# toplayer.net
KiCad netlist of a schematic drawn in Altium Designer
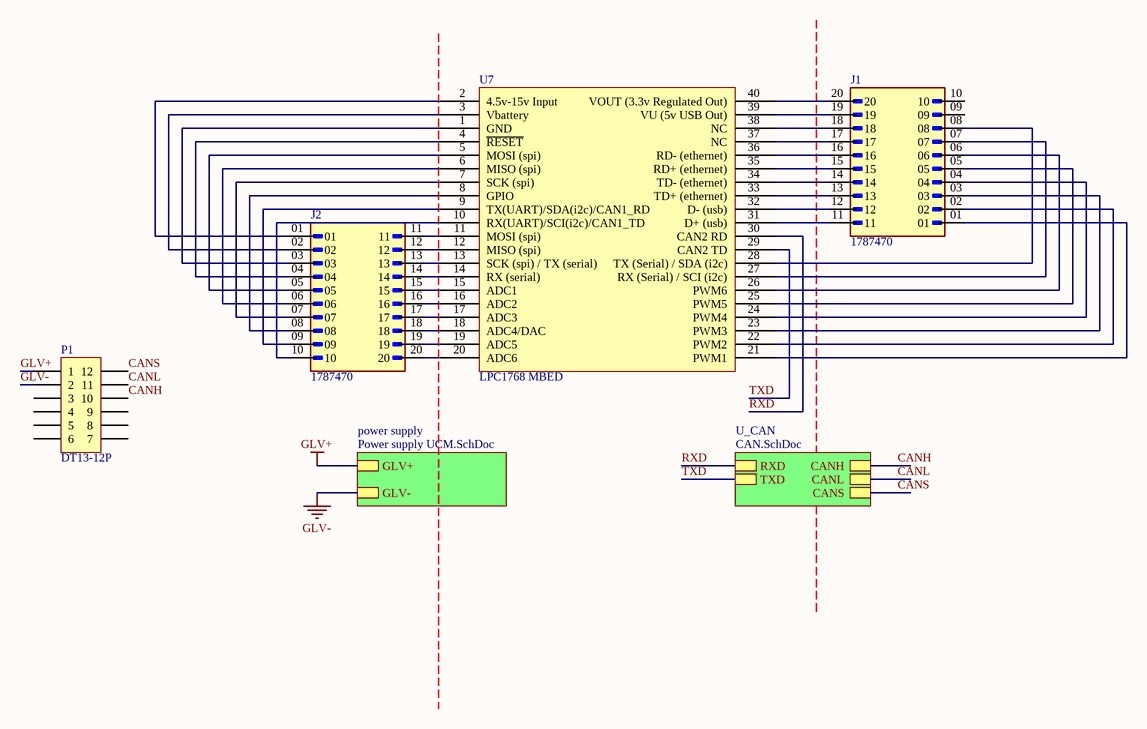
[diagram p0: toplayer.SchDoc]

(export (version "E")
  (design (tool "Eeschema 10.0.6"))
  (components
    (comp (ref "J1") (value "1787470") (footprint "PHOENIX_1787470") (libsource (lib "") (part "1787470_1")))
    (comp (ref "J2")
      (value "1787470")
      (footprint "PHOENIX_1787470")
      (libsource (lib "1787470") (part "1787470"))
    )
    (comp (ref "P1")
      (value "DT13-12P")
      (footprint "DT13-12P")
      (fields (field (name "DIGIKEY PART NUMBER") "1734-1451-ND") (field (name "CONTACT") "Nickel"))
      (libsource (lib "ts_19-standard-connectors") (part "DT13-12P"))
    )
    (comp (ref "U7")
      (value "LPC1768 MBED")
      (footprint "LPC1768 MBED")
      (description "ARM M3 mBed Enabled Microcontroller")
      (fields (field (name "MANUFACTURER") "NXP") (field (name "DIGIKEY PART NUMBER") "568-4916-ND"))
      (libsource (lib "ts_19-standard-library") (part "LPC1768 MBED"))
    )
  )
  (nets
    (net (code "1") (name "/CANH") (class "Default")
      (node (ref "P1") (pin "10") (pinfunction "10_10") (pintype "passive"))
    )
    (net (code "2") (name "/CANL") (class "Default")
      (node (ref "P1") (pin "11") (pinfunction "11_11") (pintype "passive"))
    )
    (net (code "3") (name "/CANS") (class "Default")
      (node (ref "P1") (pin "12") (pinfunction "12_12") (pintype "passive"))
    )
    (net (code "4") (name "/RXD") (class "Default")
      (node (ref "U7") (pin "30") (pinfunction "CAN2_RD_30") (pintype "passive"))
    )
    (net (code "5") (name "/TXD") (class "Default")
      (node (ref "U7") (pin "29") (pinfunction "CAN2_TD_29") (pintype "passive"))
    )
    (net (code "6") (name "GLV+") (class "Default")
      (node (ref "P1") (pin "1") (pinfunction "1_1") (pintype "power_in"))
    )
    (net (code "7") (name "GLV-") (class "Default")
      (node (ref "P1") (pin "2") (pinfunction "2_2") (pintype "power_in"))
    )
    (net (code "8") (name "Net-(J1-Pad17)") (class "Default")
      (node (ref "J1") (pin "17") (pinfunction "17_17") (pintype "passive"))
      (node (ref "U7") (pin "37") (pinfunction "NC_37") (pintype "passive"))
    )
    (net (code "9") (name "Net-(J1-Pad18)") (class "Default")
      (node (ref "J1") (pin "18") (pinfunction "18_18") (pintype "passive"))
      (node (ref "U7") (pin "38") (pinfunction "NC_38") (pintype "passive"))
    )
    (net (code "10") (name "Net-(J2-Pad05)") (class "Default")
      (node (ref "J2") (pin "05") (pinfunction "05_05") (pintype "passive"))
      (node (ref "U7") (pin "5") (pinfunction "MOSI_(spi)_5") (pintype "passive"))
    )
    (net (code "11") (name "Net-(J2-Pad06)") (class "Default")
      (node (ref "J2") (pin "06") (pinfunction "06_06") (pintype "passive"))
      (node (ref "U7") (pin "6") (pinfunction "MISO_(spi)_6") (pintype "passive"))
    )
    (net (code "12") (name "Net-(J2-Pad11)") (class "Default")
      (node (ref "J2") (pin "11") (pinfunction "11_11") (pintype "passive"))
      (node (ref "U7") (pin "11") (pinfunction "MOSI_(spi)_11") (pintype "passive"))
    )
    (net (code "13") (name "Net-(J2-Pad12)") (class "Default")
      (node (ref "J2") (pin "12") (pinfunction "12_12") (pintype "passive"))
      (node (ref "U7") (pin "12") (pinfunction "MISO_(spi)_12") (pintype "passive"))
    )
    (net (code "14") (name "Net-(U7-4.5v-15v_Input)") (class "Default")
      (node (ref "J2") (pin "01") (pinfunction "01_01") (pintype "passive"))
      (node (ref "U7") (pin "2") (pinfunction "4.5v-15v_Input_2") (pintype "passive"))
    )
    (net (code "15") (name "Net-(U7-ADC1)") (class "Default")
      (node (ref "J2") (pin "15") (pinfunction "15_15") (pintype "passive"))
      (node (ref "U7") (pin "15") (pinfunction "ADC1_15") (pintype "passive"))
    )
    (net (code "16") (name "Net-(U7-ADC2)") (class "Default")
      (node (ref "J2") (pin "16") (pinfunction "16_16") (pintype "passive"))
      (node (ref "U7") (pin "16") (pinfunction "ADC2_16") (pintype "passive"))
    )
    (net (code "17") (name "Net-(U7-ADC3)") (class "Default")
      (node (ref "J2") (pin "17") (pinfunction "17_17") (pintype "passive"))
      (node (ref "U7") (pin "17") (pinfunction "ADC3_17") (pintype "passive"))
    )
    (net (code "18") (name "Net-(U7-ADC4{slash}DAC)") (class "Default")
      (node (ref "J2") (pin "18") (pinfunction "18_18") (pintype "passive"))
      (node (ref "U7") (pin "18") (pinfunction "ADC4/DAC_18") (pintype "passive"))
    )
    (net (code "19") (name "Net-(U7-ADC5)") (class "Default")
      (node (ref "J2") (pin "19") (pinfunction "19_19") (pintype "passive"))
      (node (ref "U7") (pin "19") (pinfunction "ADC5_19") (pintype "passive"))
    )
    (net (code "20") (name "Net-(U7-ADC6)") (class "Default")
      (node (ref "J2") (pin "20") (pinfunction "20_20") (pintype "passive"))
      (node (ref "U7") (pin "20") (pinfunction "ADC6_20") (pintype "passive"))
    )
    (net (code "21") (name "Net-(U7-D+_(usb))") (class "Default")
      (node (ref "J1") (pin "11") (pinfunction "11_11") (pintype "passive"))
      (node (ref "U7") (pin "31") (pinfunction "D+_(usb)_31") (pintype "passive"))
    )
    (net (code "22") (name "Net-(U7-D-_(usb))") (class "Default")
      (node (ref "J1") (pin "12") (pinfunction "12_12") (pintype "passive"))
      (node (ref "U7") (pin "32") (pinfunction "D-_(usb)_32") (pintype "passive"))
    )
    (net (code "23") (name "Net-(U7-GND)") (class "Default")
      (node (ref "J2") (pin "03") (pinfunction "03_03") (pintype "passive"))
      (node (ref "U7") (pin "1") (pinfunction "GND_1") (pintype "passive"))
    )
    (net (code "24") (name "Net-(U7-GPIO)") (class "Default")
      (node (ref "J2") (pin "08") (pinfunction "08_08") (pintype "passive"))
      (node (ref "U7") (pin "8") (pinfunction "GPIO_8") (pintype "passive"))
    )
    (net (code "25") (name "Net-(U7-PWM1)") (class "Default")
      (node (ref "J1") (pin "01") (pinfunction "01_01") (pintype "passive"))
      (node (ref "U7") (pin "21") (pinfunction "PWM1_21") (pintype "passive"))
    )
    (net (code "26") (name "Net-(U7-PWM2)") (class "Default")
      (node (ref "J1") (pin "02") (pinfunction "02_02") (pintype "passive"))
      (node (ref "U7") (pin "22") (pinfunction "PWM2_22") (pintype "passive"))
    )
    (net (code "27") (name "Net-(U7-PWM3)") (class "Default")
      (node (ref "J1") (pin "03") (pinfunction "03_03") (pintype "passive"))
      (node (ref "U7") (pin "23") (pinfunction "PWM3_23") (pintype "passive"))
    )
    (net (code "28") (name "Net-(U7-PWM4)") (class "Default")
      (node (ref "J1") (pin "04") (pinfunction "04_04") (pintype "passive"))
      (node (ref "U7") (pin "24") (pinfunction "PWM4_24") (pintype "passive"))
    )
    (net (code "29") (name "Net-(U7-PWM5)") (class "Default")
      (node (ref "J1") (pin "05") (pinfunction "05_05") (pintype "passive"))
      (node (ref "U7") (pin "25") (pinfunction "PWM5_25") (pintype "passive"))
    )
    (net (code "30") (name "Net-(U7-PWM6)") (class "Default")
      (node (ref "J1") (pin "06") (pinfunction "06_06") (pintype "passive"))
      (node (ref "U7") (pin "26") (pinfunction "PWM6_26") (pintype "passive"))
    )
    (net (code "31") (name "Net-(U7-RD+_(ethernet))") (class "Default")
      (node (ref "J1") (pin "15") (pinfunction "15_15") (pintype "passive"))
      (node (ref "U7") (pin "35") (pinfunction "RD+_(ethernet)_35") (pintype "passive"))
    )
    (net (code "32") (name "Net-(U7-RD-_(ethernet))") (class "Default")
      (node (ref "J1") (pin "16") (pinfunction "16_16") (pintype "passive"))
      (node (ref "U7") (pin "36") (pinfunction "RD-_(ethernet)_36") (pintype "passive"))
    )
    (net (code "33") (name "Net-(U7-RX(UART){slash}SCI(i2c){slash}CAN1_TD)") (class "Default")
      (node (ref "J2") (pin "10") (pinfunction "10_10") (pintype "passive"))
      (node (ref "U7") (pin "10") (pinfunction "RX(UART)/SCI(i2c)/CAN1_TD_10") (pintype "passive"))
    )
    (net (code "34") (name "Net-(U7-RX_(Serial)_{slash}_SCI_(i2c))") (class "Default")
      (node (ref "J1") (pin "07") (pinfunction "07_07") (pintype "passive"))
      (node (ref "U7") (pin "27") (pinfunction "RX_(Serial)_/_SCI_(i2c)_27") (pintype "passive"))
    )
    (net (code "35") (name "Net-(U7-RX_(serial))") (class "Default")
      (node (ref "J2") (pin "14") (pinfunction "14_14") (pintype "passive"))
      (node (ref "U7") (pin "14") (pinfunction "RX_(serial)_14") (pintype "passive"))
    )
    (net (code "36") (name "Net-(U7-SCK_(spi))") (class "Default")
      (node (ref "J2") (pin "07") (pinfunction "07_07") (pintype "passive"))
      (node (ref "U7") (pin "7") (pinfunction "SCK_(spi)_7") (pintype "passive"))
    )
    (net (code "37") (name "Net-(U7-SCK_(spi)_{slash}_TX_(serial))") (class "Default")
      (node (ref "J2") (pin "13") (pinfunction "13_13") (pintype "passive"))
      (node (ref "U7") (pin "13") (pinfunction "SCK_(spi)_/_TX_(serial)_13") (pintype "passive"))
    )
    (net (code "38") (name "Net-(U7-TD+_(ethernet))") (class "Default")
      (node (ref "J1") (pin "13") (pinfunction "13_13") (pintype "passive"))
      (node (ref "U7") (pin "33") (pinfunction "TD+_(ethernet)_33") (pintype "passive"))
    )
    (net (code "39") (name "Net-(U7-TD-_(ethernet))") (class "Default")
      (node (ref "J1") (pin "14") (pinfunction "14_14") (pintype "passive"))
      (node (ref "U7") (pin "34") (pinfunction "TD-_(ethernet)_34") (pintype "passive"))
    )
    (net (code "40") (name "Net-(U7-TX(UART){slash}SDA(i2c){slash}CAN1_RD)") (class "Default")
      (node (ref "J2") (pin "09") (pinfunction "09_09") (pintype "passive"))
      (node (ref "U7") (pin "9") (pinfunction "TX(UART)/SDA(i2c)/CAN1_RD_9") (pintype "passive"))
    )
    (net (code "41") (name "Net-(U7-TX_(Serial)_{slash}_SDA_(i2c))") (class "Default")
      (node (ref "J1") (pin "08") (pinfunction "08_08") (pintype "passive"))
      (node (ref "U7") (pin "28") (pinfunction "TX_(Serial)_/_SDA_(i2c)_28") (pintype "passive"))
    )
    (net (code "42") (name "Net-(U7-VOUT_(3.3v_Regulated_Out))") (class "Default")
      (node (ref "J1") (pin "20") (pinfunction "20_20") (pintype "passive"))
      (node (ref "U7") (pin "40") (pinfunction "VOUT_(3.3v_Regulated_Out)_40") (pintype "passive"))
    )
    (net (code "43") (name "Net-(U7-VU_(5v_USB_Out))") (class "Default")
      (node (ref "J1") (pin "19") (pinfunction "19_19") (pintype "passive"))
      (node (ref "U7") (pin "39") (pinfunction "VU_(5v_USB_Out)_39") (pintype "passive"))
    )
    (net (code "44") (name "Net-(U7-Vbattery)") (class "Default")
      (node (ref "J2") (pin "02") (pinfunction "02_02") (pintype "passive"))
      (node (ref "U7") (pin "3") (pinfunction "Vbattery_3") (pintype "passive"))
    )
    (net (code "45") (name "Net-(U7-~{RESET})") (class "Default")
      (node (ref "J2") (pin "04") (pinfunction "04_04") (pintype "passive"))
      (node (ref "U7") (pin "4") (pinfunction "~{RESET}_4") (pintype "passive"))
    )
    (net (code "46") (name "unconnected-(J1-Pad09)") (class "Default")
      (node (ref "J1") (pin "09") (pinfunction "09_09") (pintype "passive"))
    )
    (net (code "47") (name "unconnected-(J1-Pad10)") (class "Default")
      (node (ref "J1") (pin "10") (pinfunction "10_10") (pintype "passive"))
    )
    (net (code "48") (name "unconnected-(P1-Pad3)") (class "Default")
      (node (ref "P1") (pin "3") (pinfunction "3_3") (pintype "power_in"))
    )
    (net (code "49") (name "unconnected-(P1-Pad4)") (class "Default")
      (node (ref "P1") (pin "4") (pinfunction "4_4") (pintype "power_in"))
    )
    (net (code "50") (name "unconnected-(P1-Pad5)") (class "Default")
      (node (ref "P1") (pin "5") (pinfunction "5_5") (pintype "power_in"))
    )
    (net (code "51") (name "unconnected-(P1-Pad6)") (class "Default")
      (node (ref "P1") (pin "6") (pinfunction "6_6") (pintype "power_in"))
    )
    (net (code "52") (name "unconnected-(P1-Pad7)") (class "Default")
      (node (ref "P1") (pin "7") (pinfunction "7_7") (pintype "passive"))
    )
    (net (code "53") (name "unconnected-(P1-Pad8)") (class "Default")
      (node (ref "P1") (pin "8") (pinfunction "8_8") (pintype "passive"))
    )
    (net (code "54") (name "unconnected-(P1-Pad9)") (class "Default")
      (node (ref "P1") (pin "9") (pinfunction "9_9") (pintype "passive"))
    )
  )
)
